# QRE1113-1.net
KiCad netlist of a schematic drawn in Altium Designer
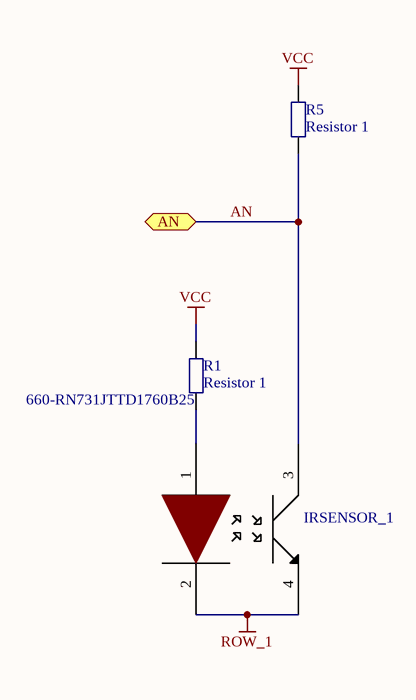
[diagram p0: QRE1113-1.SchDoc]

(export (version "E")
  (design (tool "Eeschema 10.0.6"))
  (components
    (comp (ref "IRSENSOR_1")
      (value "QRE1113GR")
      (footprint "QRE1113:QRE1113GR")
      (libsource (lib "Keyboard Library") (part "QRE1113GR"))
    )
    (comp (ref "R1")
      (value "Resistor 1")
      (footprint "R-0603")
      (description "Resistor")
      (fields (field (name "SUPPLIER PART NUMBER 2") "660-RN731JTTD1760B25"))
      (libsource (lib "Max Library") (part "Resistor 1"))
    )
    (comp (ref "R5")
      (value "Resistor 1")
      (footprint "R-0603")
      (description "Resistor")
      (libsource (lib "Max Library") (part "Resistor 1"))
    )
  )
  (nets
    (net (code "1") (name "/AN") (class "Default")
      (node (ref "IRSENSOR_1") (pin "3") (pinfunction "3_3") (pintype "passive"))
      (node (ref "R5") (pin "2") (pinfunction "2_2") (pintype "passive"))
    )
    (net (code "2") (name "Net-(IRSENSOR_1-Pad1)") (class "Default")
      (node (ref "IRSENSOR_1") (pin "1") (pinfunction "1_1") (pintype "passive"))
      (node (ref "R1") (pin "2") (pinfunction "2_2") (pintype "passive"))
    )
    (net (code "3") (name "ROW_1") (class "Default")
      (node (ref "IRSENSOR_1") (pin "2") (pinfunction "2_2") (pintype "passive"))
      (node (ref "IRSENSOR_1") (pin "4") (pinfunction "4_4") (pintype "passive"))
    )
    (net (code "4") (name "VCC") (class "Default")
      (node (ref "R1") (pin "1") (pinfunction "1_1") (pintype "passive"))
      (node (ref "R5") (pin "1") (pinfunction "1_1") (pintype "passive"))
    )
  )
)
